# 08_Zynq_Config_ADC.net
KiCad netlist of a schematic drawn in Altium Designer
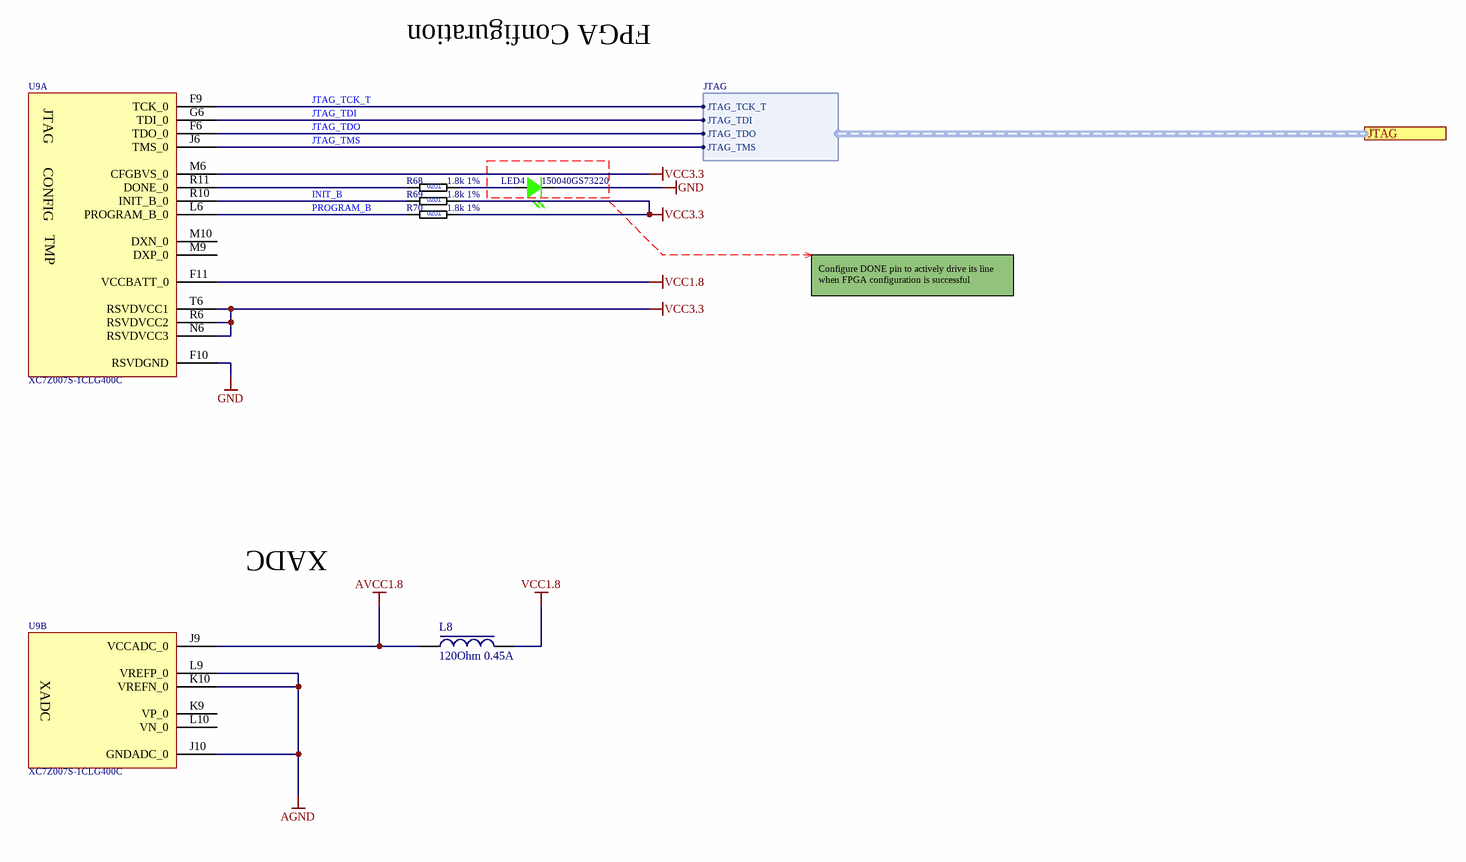
[diagram p0: 08_Zynq Config_ADC.SchDoc]

(export (version "E")
  (design (tool "Eeschema 10.0.6"))
  (components
    (comp (ref "L8")
      (value "120Ohm 0.45A")
      (footprint "Zynq-Feather-HD:INDC0603X03L")
      (description "Ferrite Bead 0201 120Ohm 0.45A 25%")
      (fields (field (name "MANUFACTURER") "Taiyo Yuden"))
      (libsource (lib "Zynq-Feather-HD") (part "FLT_0201_120Ohm_0.45A"))
    )
    (comp (ref "LED4")
      (value "150040GS73220")
      (footprint "Zynq-Feather-HD:WL-SMCC_0402_H=0.25mm")
      (description "Standard LEDs - SMD WL-SMCC SMT LED Mono-color")
      (libsource (lib "Zynq-Feather-HD") (part "150040GS73220_SMD WL-SMCC SMT LED Mono-color"))
    )
    (comp (ref "R68")
      (value "1.8k 1%")
      (footprint "Zynq-Feather-HD:RESC0603X03L")
      (description "Thick Film Resistors - SMD 1.8K OHM 1%")
      (libsource (lib "Zynq-Feather-HD") (part "RES_0201_1.8k_1%"))
    )
    (comp (ref "R69")
      (value "1.8k 1%")
      (footprint "Zynq-Feather-HD:RESC0603X03L")
      (description "Thick Film Resistors - SMD 1.8K OHM 1%")
      (libsource (lib "Zynq-Feather-HD") (part "RES_0201_1.8k_1%"))
    )
    (comp (ref "R70")
      (value "1.8k 1%")
      (footprint "Zynq-Feather-HD:RESC0603X03L")
      (description "Thick Film Resistors - SMD 1.8K OHM 1%")
      (libsource (lib "Zynq-Feather-HD") (part "RES_0201_1.8k_1%"))
    )
    (comp (ref "U9")
      (value "XC7Z007S-1CLG400C")
      (footprint "Zynq-Feather-HD:BGA400C80P20X20_1700X1700X160")
      (description "XC7Z007S-1CLG400C_Processors - Application Specialised")
      (libsource (lib "Zynq-Feather-HD") (part "XC7Z007S-1CLG400C_Processors - Application Specialised"))
    )
  )
  (nets
    (net (code "3") (name "/INIT_B") (class "Default")
      (node (ref "R69") (pin "1") (pinfunction "1_1") (pintype "passive"))
      (node (ref "U9") (pin "R10") (pinfunction "INIT_B_0_R10") (pintype "passive"))
    )
    (net (code "4") (name "/JTAG_TCK_T") (class "Default")
      (node (ref "U9") (pin "F9") (pinfunction "TCK_0_F9") (pintype "passive"))
    )
    (net (code "5") (name "/JTAG_TDI") (class "Default")
      (node (ref "U9") (pin "G6") (pinfunction "TDI_0_G6") (pintype "passive"))
    )
    (net (code "6") (name "/JTAG_TDO") (class "Default")
      (node (ref "U9") (pin "F6") (pinfunction "TDO_0_F6") (pintype "passive"))
    )
    (net (code "7") (name "/JTAG_TMS") (class "Default")
      (node (ref "U9") (pin "J6") (pinfunction "TMS_0_J6") (pintype "passive"))
    )
    (net (code "8") (name "/PROGRAM_B") (class "Default")
      (node (ref "R70") (pin "1") (pinfunction "1_1") (pintype "passive"))
      (node (ref "U9") (pin "L6") (pinfunction "PROGRAM_B_0_L6") (pintype "passive"))
    )
    (net (code "10") (name "AGND") (class "Default")
      (node (ref "U9") (pin "J10") (pinfunction "GNDADC_0_J10") (pintype "passive"))
      (node (ref "U9") (pin "K10") (pinfunction "VREFN_0_K10") (pintype "passive"))
      (node (ref "U9") (pin "L9") (pinfunction "VREFP_0_L9") (pintype "passive"))
    )
    (net (code "11") (name "AVCC1.8") (class "Default")
      (node (ref "L8") (pin "2") (pinfunction "2_2") (pintype "passive"))
      (node (ref "U9") (pin "J9") (pinfunction "VCCADC_0_J9") (pintype "passive"))
    )
    (net (code "12") (name "GND") (class "Default")
      (node (ref "LED4") (pin "1") (pinfunction "1_1") (pintype "passive"))
      (node (ref "U9") (pin "F10") (pinfunction "RSVDGND_F10") (pintype "passive"))
    )
    (net (code "13") (name "Net-(LED4-Pad2)") (class "Default")
      (node (ref "LED4") (pin "2") (pinfunction "2_2") (pintype "passive"))
      (node (ref "R68") (pin "2") (pinfunction "2_2") (pintype "passive"))
    )
    (net (code "14") (name "Net-(U9A-DONE_0)") (class "Default")
      (node (ref "R68") (pin "1") (pinfunction "1_1") (pintype "passive"))
      (node (ref "U9") (pin "R11") (pinfunction "DONE_0_R11") (pintype "passive"))
    )
    (net (code "15") (name "VCC1.8") (class "Default")
      (node (ref "L8") (pin "1") (pinfunction "1_1") (pintype "passive"))
      (node (ref "U9") (pin "F11") (pinfunction "VCCBATT_0_F11") (pintype "passive"))
    )
    (net (code "16") (name "VCC3.3") (class "Default")
      (node (ref "R69") (pin "2") (pinfunction "2_2") (pintype "passive"))
      (node (ref "R70") (pin "2") (pinfunction "2_2") (pintype "passive"))
      (node (ref "U9") (pin "M6") (pinfunction "CFGBVS_0_M6") (pintype "passive"))
      (node (ref "U9") (pin "N6") (pinfunction "RSVDVCC3_N6") (pintype "passive"))
      (node (ref "U9") (pin "R6") (pinfunction "RSVDVCC2_R6") (pintype "passive"))
      (node (ref "U9") (pin "T6") (pinfunction "RSVDVCC1_T6") (pintype "passive"))
    )
    (net (code "17") (name "unconnected-(U9A-DXN_0-PadM10)") (class "Default")
      (node (ref "U9") (pin "M10") (pinfunction "DXN_0_M10") (pintype "passive"))
    )
    (net (code "18") (name "unconnected-(U9A-DXP_0-PadM9)") (class "Default")
      (node (ref "U9") (pin "M9") (pinfunction "DXP_0_M9") (pintype "passive"))
    )
    (net (code "19") (name "unconnected-(U9B-VN_0-PadL10)") (class "Default")
      (node (ref "U9") (pin "L10") (pinfunction "VN_0_L10") (pintype "passive"))
    )
    (net (code "20") (name "unconnected-(U9B-VP_0-PadK9)") (class "Default")
      (node (ref "U9") (pin "K9") (pinfunction "VP_0_K9") (pintype "passive"))
    )
  )
)
